# 0_96in_TFT.net
KiCad netlist of a schematic drawn in EasyEDA Pro
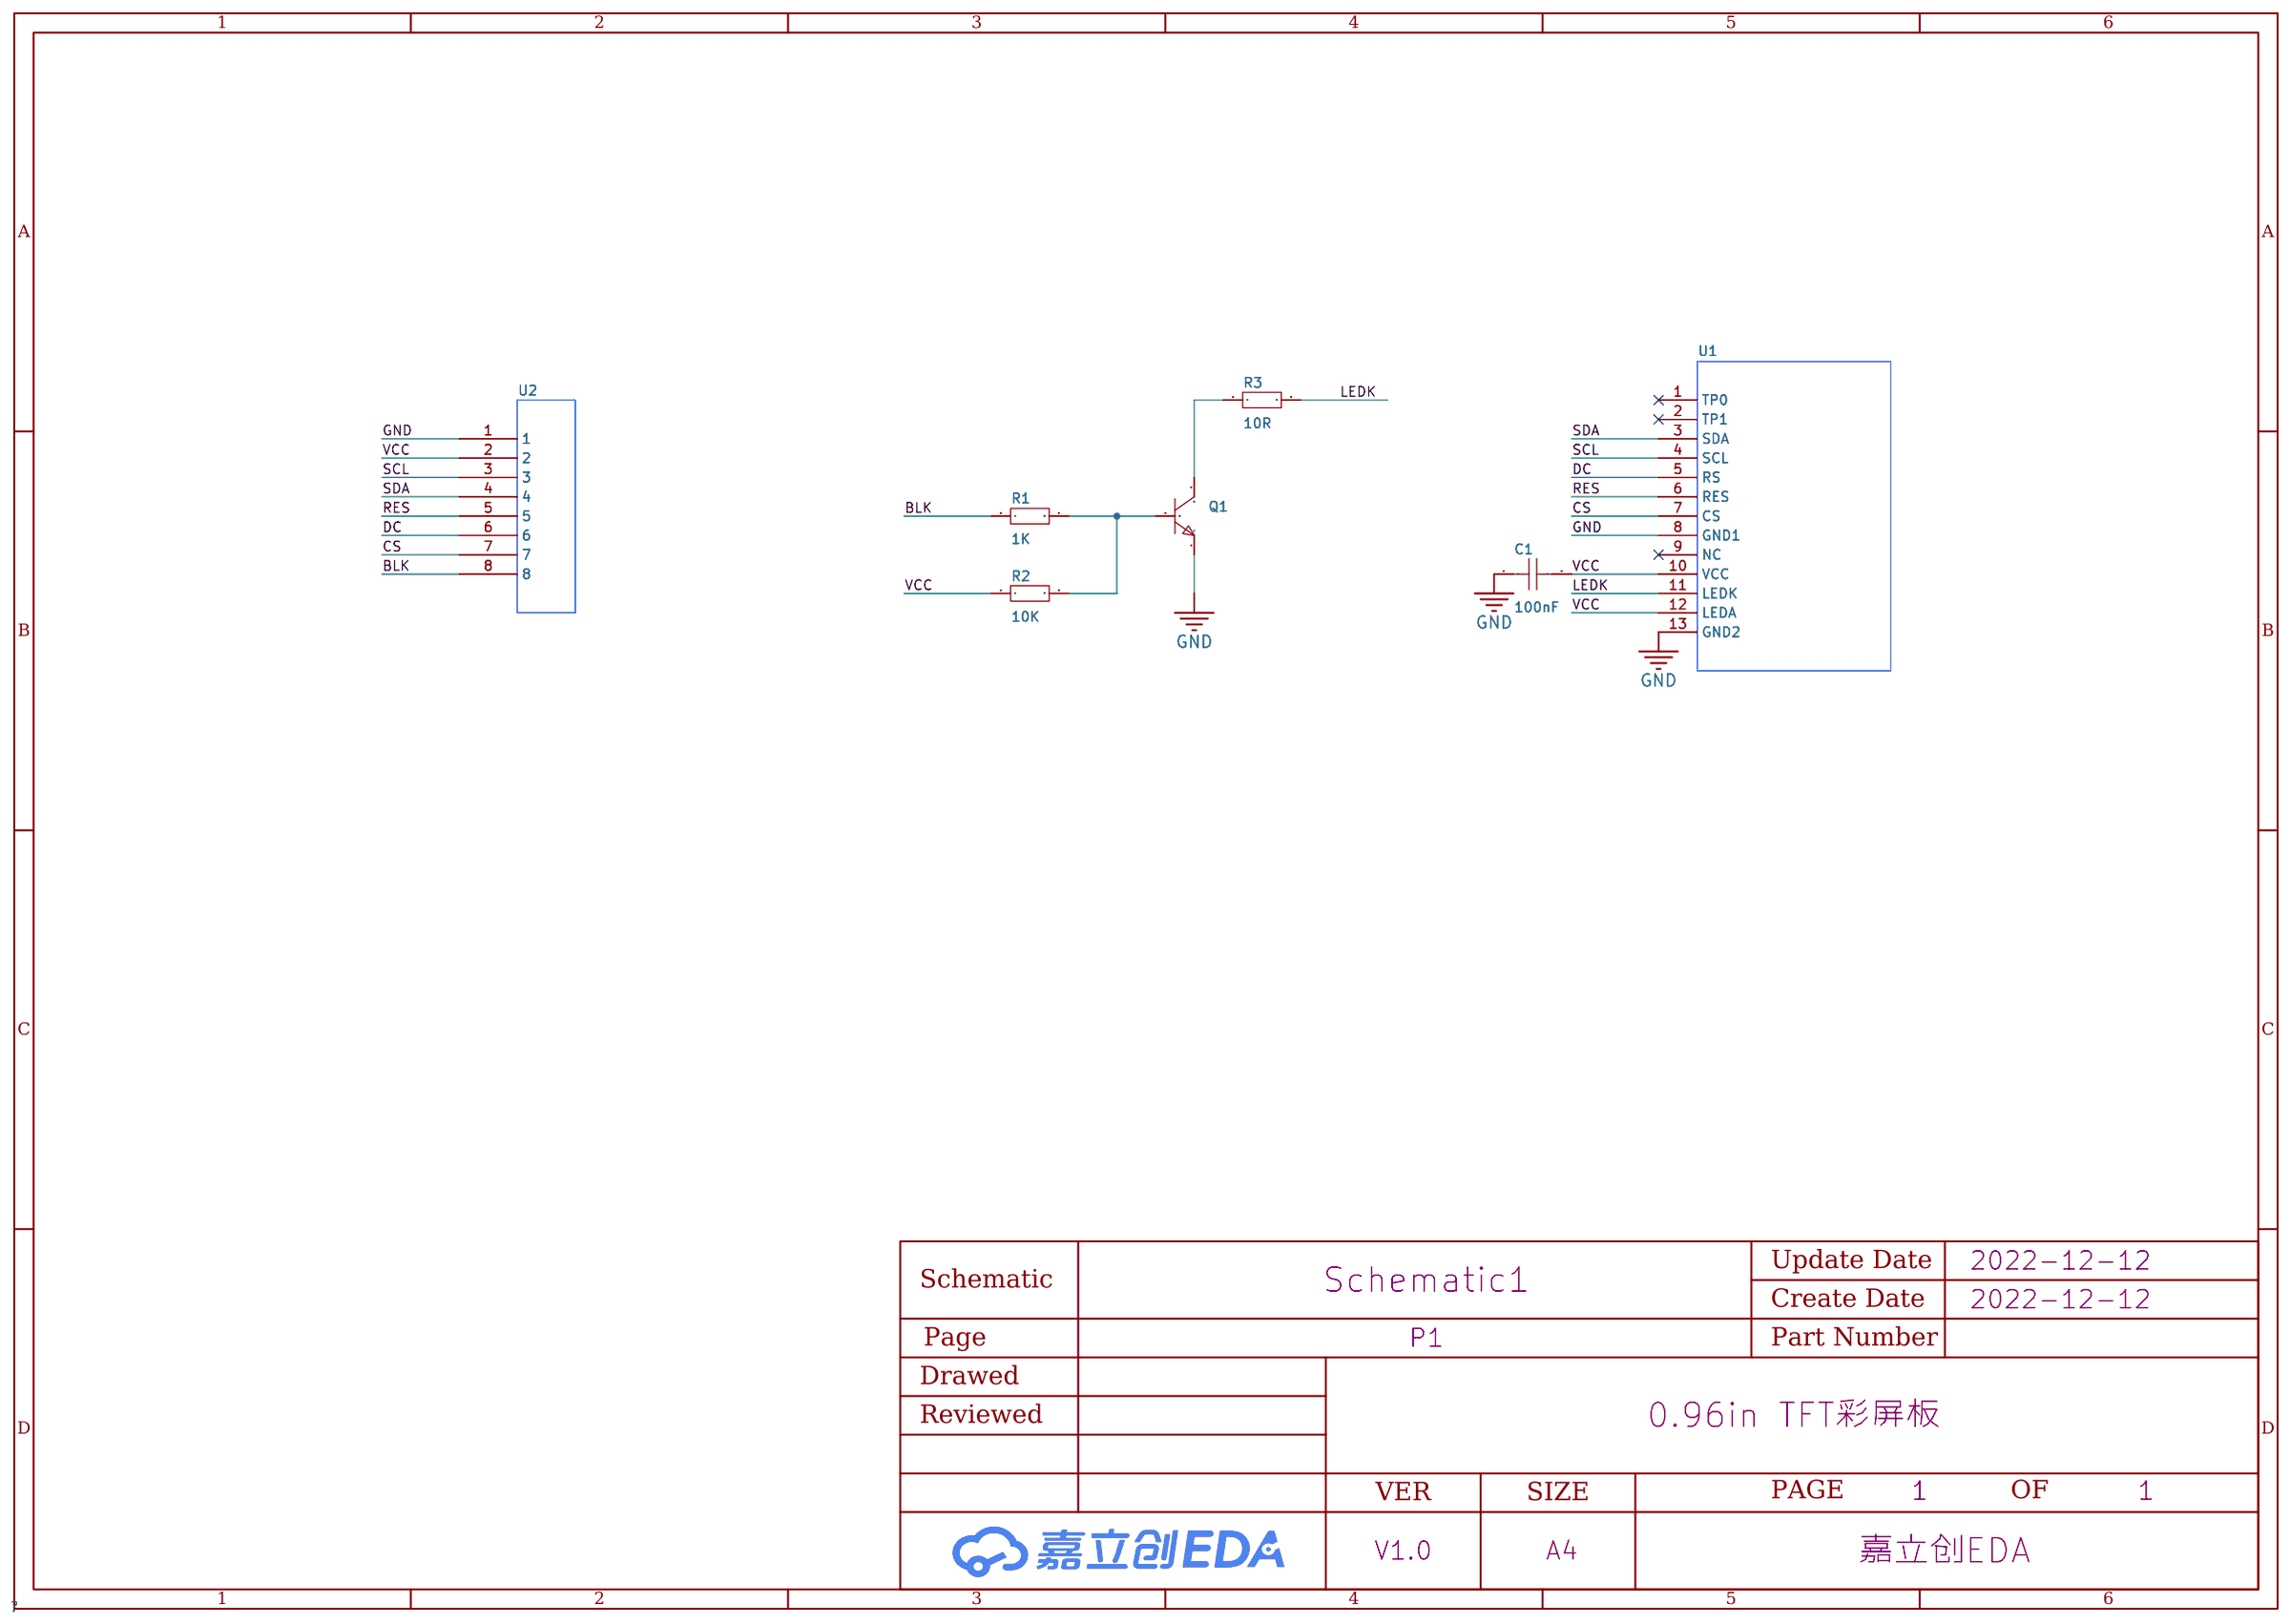
[diagram p0: schematic sheet]

(export (version "E")
  (design (tool "Eeschema 10.0.6"))
  (components
    (comp (ref "C1")
      (value "100nF")
      (footprint "easyedapro:C0603")
      (libsource (lib "easyedapro") (part "C1210X7R475K630NT"))
    )
    (comp (ref "Q1")
      (value "~")
      (footprint "easyedapro:SOT-23_L2.9-W1.3-P1.90-LS2.4-BR")
      (libsource (lib "easyedapro") (part "NPN"))
    )
    (comp (ref "R1") (value "1K") (footprint "easyedapro:R0603") (libsource (lib "easyedapro") (part "电阻")))
    (comp (ref "R2") (value "10K") (footprint "easyedapro:R0603") (libsource (lib "easyedapro") (part "电阻")))
    (comp (ref "R3") (value "10R") (footprint "easyedapro:R0603") (libsource (lib "easyedapro") (part "电阻")))
    (comp (ref "U1")
      (value "~")
      (footprint "easyedapro:LCD 0.96 13Pin")
      (libsource (lib "easyedapro") (part "LCD 0.96 13Pin"))
    )
    (comp (ref "U2")
      (value "~")
      (footprint "easyedapro:Header-8P-2.54")
      (libsource (lib "easyedapro") (part "Header-8P-2.54"))
    )
  )
  (nets
    (net (code "1") (name "/BLK") (class "Default")
      (node (ref "R1") (pin "1") (pinfunction "1_1") (pintype "input"))
      (node (ref "U2") (pin "8") (pinfunction "8_8") (pintype "input"))
    )
    (net (code "2") (name "/CS") (class "Default")
      (node (ref "U1") (pin "7") (pinfunction "CS_7") (pintype "input"))
      (node (ref "U2") (pin "7") (pinfunction "7_7") (pintype "input"))
    )
    (net (code "3") (name "/DC") (class "Default")
      (node (ref "U1") (pin "5") (pinfunction "RS_5") (pintype "input"))
      (node (ref "U2") (pin "6") (pinfunction "6_6") (pintype "input"))
    )
    (net (code "4") (name "/LEDK") (class "Default")
      (node (ref "R3") (pin "2") (pinfunction "2_2") (pintype "input"))
      (node (ref "U1") (pin "11") (pinfunction "LEDK_11") (pintype "input"))
    )
    (net (code "5") (name "/RES") (class "Default")
      (node (ref "U1") (pin "6") (pinfunction "RES_6") (pintype "input"))
      (node (ref "U2") (pin "5") (pinfunction "5_5") (pintype "input"))
    )
    (net (code "6") (name "/SCL") (class "Default")
      (node (ref "U1") (pin "4") (pinfunction "SCL_4") (pintype "input"))
      (node (ref "U2") (pin "3") (pinfunction "3_3") (pintype "input"))
    )
    (net (code "7") (name "/SDA") (class "Default")
      (node (ref "U1") (pin "3") (pinfunction "SDA_3") (pintype "input"))
      (node (ref "U2") (pin "4") (pinfunction "4_4") (pintype "input"))
    )
    (net (code "8") (name "/VCC") (class "Default")
      (node (ref "C1") (pin "2") (pinfunction "2_2") (pintype "input"))
      (node (ref "R2") (pin "1") (pinfunction "1_1") (pintype "input"))
      (node (ref "U1") (pin "10") (pinfunction "VCC_10") (pintype "input"))
      (node (ref "U1") (pin "12") (pinfunction "LEDA_12") (pintype "input"))
      (node (ref "U2") (pin "2") (pinfunction "2_2") (pintype "input"))
    )
    (net (code "9") (name "GND") (class "Default")
      (node (ref "C1") (pin "1") (pinfunction "1_1") (pintype "input"))
      (node (ref "Q1") (pin "2") (pinfunction "2_2") (pintype "unspecified"))
      (node (ref "U1") (pin "13") (pinfunction "GND2_13") (pintype "input"))
      (node (ref "U1") (pin "8") (pinfunction "GND1_8") (pintype "input"))
      (node (ref "U2") (pin "1") (pinfunction "1_1") (pintype "input"))
    )
    (net (code "10") (name "Net-(Q1-Pad1)") (class "Default")
      (node (ref "Q1") (pin "1") (pinfunction "1_1") (pintype "unspecified"))
      (node (ref "R1") (pin "2") (pinfunction "2_2") (pintype "input"))
      (node (ref "R2") (pin "2") (pinfunction "2_2") (pintype "input"))
    )
    (net (code "11") (name "Net-(Q1-Pad3)") (class "Default")
      (node (ref "Q1") (pin "3") (pinfunction "3_3") (pintype "unspecified"))
      (node (ref "R3") (pin "1") (pinfunction "1_1") (pintype "input"))
    )
    (net (code "12") (name "unconnected-(U1-NC-Pad9)") (class "Default")
      (node (ref "U1") (pin "9") (pinfunction "NC_9") (pintype "input+no_connect"))
    )
    (net (code "13") (name "unconnected-(U1-TP0-Pad1)") (class "Default")
      (node (ref "U1") (pin "1") (pinfunction "TP0_1") (pintype "input+no_connect"))
    )
    (net (code "14") (name "unconnected-(U1-TP1-Pad2)") (class "Default")
      (node (ref "U1") (pin "2") (pinfunction "TP1_2") (pintype "input+no_connect"))
    )
  )
)
